# Power.net
KiCad netlist of a schematic drawn in Altium Designer
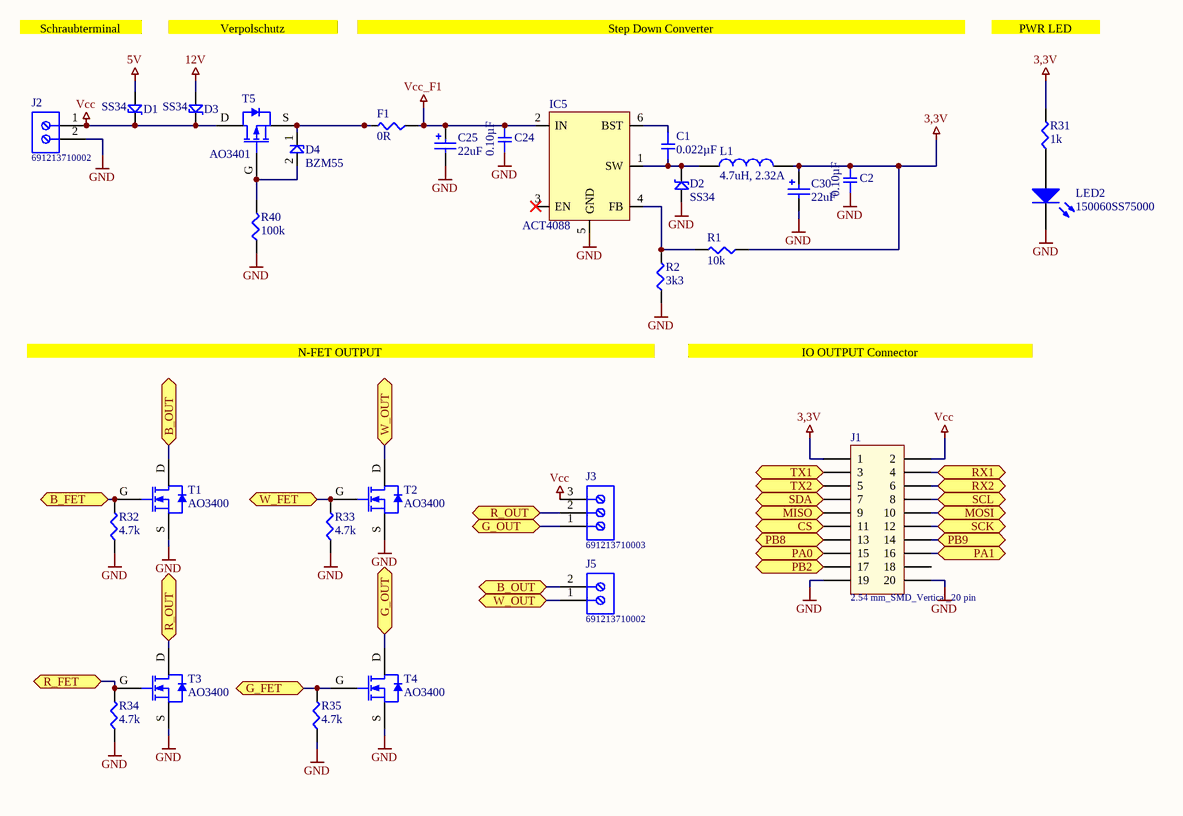
[diagram p0: Power.SchDoc]

(export (version "E")
  (design (tool "Eeschema 10.0.6"))
  (components
    (comp (ref "C1")
      (value "0.022µF")
      (footprint "SMD-0603C")
      (description "CAP CER 0.022UF 50V X7R 0603")
      (fields
        (field (name "DIGI-KEY PART NUMBER") "490-5851-1-ND")
        (field (name "PART NUMBER") "GCJ188R71H223KA01D")
      )
      (libsource (lib "capacitor_murata_0603") (part "GCJ188R71H223KA01D"))
    )
    (comp (ref "C2")
      (value "0.10µF")
      (footprint "SMD-0603C")
      (description "CAP CER 0.1UF 16V X7R 0603")
      (fields
        (field (name "DIGI-KEY PART NUMBER") "490-8015-1-ND")
        (field (name "PART NUMBER") "GCM188R71C104KA37J")
      )
      (libsource (lib "capacitor_murata_0603") (part "GCM188R71C104KA37J"))
    )
    (comp (ref "C24")
      (value "0.10µF")
      (footprint "SMD-0603C")
      (description "CAP CER 0.1UF 16V X7R 0603")
      (fields
        (field (name "DIGI-KEY PART NUMBER") "490-8015-1-ND")
        (field (name "PART NUMBER") "GCM188R71C104KA37J")
      )
      (libsource (lib "capacitor_murata_0603") (part "GCM188R71C104KA37J"))
    )
    (comp (ref "C25")
      (value "22uF")
      (footprint "WCAP-ASLI_4x5.5")
      (description "WCAP-ASLI Aluminum Electrolytic Capacitors, size Ф4x5.5mm, 6.3V DC, 22uF")
      (fields (field (name "PART NUMBER") "865080140001") (field (name "PUBLISHER") "Wurth Elektronik"))
      (libsource (lib "ALTIUM-WCAP-ASLI-rev17a") (part "865080140001"))
    )
    (comp (ref "C30")
      (value "22uF")
      (footprint "WCAP-ASLI_4x5.5")
      (description "WCAP-ASLI Aluminum Electrolytic Capacitors, size Ф4x5.5mm, 6.3V DC, 22uF")
      (fields (field (name "PART NUMBER") "865080140001") (field (name "PUBLISHER") "Wurth Elektronik"))
      (libsource (lib "ALTIUM-WCAP-ASLI-rev17a") (part "865080140001"))
    )
    (comp (ref "D1")
      (value "SS34")
      (footprint "B240A")
      (description "Shottkydiode")
      (libsource (lib "MyLibs") (part "B240A"))
    )
    (comp (ref "D2")
      (value "SS34")
      (footprint "B240A")
      (description "Shottkydiode")
      (libsource (lib "MyLibs") (part "B240A"))
    )
    (comp (ref "D3")
      (value "SS34")
      (footprint "B240A")
      (description "Shottkydiode")
      (libsource (lib "MyLibs") (part "B240A"))
    )
    (comp (ref "D4") (value "BZM55") (footprint "SMD-0603-RES") (libsource (lib "MyLibs") (part "BZM55")))
    (comp (ref "F1")
      (value "0R")
      (footprint "SMD-0603-RES")
      (description "RES SMD 1K OHM 1% 1/10W 0603")
      (fields
        (field (name "PART NUMBER") "ERJ-3EKF1001V")
        (field (name "DIGI-KEY PART NUMBER") "P1.00KHCT-ND")
      )
      (libsource (lib "Panasonic_ERJ_0603") (part "ERJ-3EKF1001V"))
    )
    (comp (ref "IC5") (value "ACT4088") (footprint "SOT23-6") (libsource (lib "MyLibs") (part "ACT4088")))
    (comp (ref "J1")
      (value "2.54 mm_SMD_Vertical_20 pin")
      (footprint "61002021121")
      (description "Pin Header WR-PHD, pitch 2.54 mm, SMD, Vertical, dual row, 20 pin")
      (fields (field (name "PART NUMBER") "61002021121") (field (name "PUBLISHER") "Wurth Elektronik"))
      (libsource (lib "Altium_WR-PHD_PIN_HEADER_2_54 (rev18a)") (part "61002021121"))
    )
    (comp (ref "J2")
      (value "691213710002")
      (footprint "691213710002")
      (description "Serie 213 - 5.00 mm Horizontal Entry Modular with RisingCage Clamp WR-TBL, 2 pin")
      (fields (field (name "PUBLISHER") "Wurth Elektronik"))
      (libsource (lib "Altium_TBL_RISING_CAGE_SYSTEM (rev18b)") (part "691213710002"))
    )
    (comp (ref "J3")
      (value "691213710003")
      (footprint "691213710003")
      (description "Serie 213 - 5.00 mm Horizontal Entry Modular with RisingCage Clamp WR-TBL, 3 pin")
      (fields (field (name "PUBLISHER") "Wurth Elektronik"))
      (libsource (lib "Altium_TBL_RISING_CAGE_SYSTEM (rev18b)") (part "691213710003"))
    )
    (comp (ref "J5")
      (value "691213710002")
      (footprint "691213710002")
      (description "Serie 213 - 5.00 mm Horizontal Entry Modular with RisingCage Clamp WR-TBL, 2 pin")
      (fields (field (name "PUBLISHER") "Wurth Elektronik"))
      (libsource (lib "Altium_TBL_RISING_CAGE_SYSTEM (rev18b)") (part "691213710002"))
    )
    (comp (ref "L1")
      (value "4.7uH, 2.32A")
      (footprint "WE-PD_7332")
      (description "WE-PD SMT Power Inductor, size 7332, 4.7uH, 2.32A")
      (fields (field (name "PART NUMBER") "744778004") (field (name "PUBLISHER") "Wurth Elektronik"))
      (libsource (lib "ALTIUM-WE-PD-rev19b") (part "744778004"))
    )
    (comp (ref "LED2")
      (value "150060SS75000")
      (footprint "0603_A")
      (description "SMD mono-color Chip LED, WL-SMCW, Super Red")
      (libsource (lib "WL-SMCW SMD chip LED top view mono-color waterclear") (part "150060SS75000"))
    )
    (comp (ref "R1")
      (value "10k")
      (footprint "SMD-0603-RES")
      (description "RES SMD 1K OHM 1% 1/10W 0603")
      (fields
        (field (name "PART NUMBER") "ERJ-3EKF1001V")
        (field (name "DIGI-KEY PART NUMBER") "P1.00KHCT-ND")
      )
      (libsource (lib "Panasonic_ERJ_0603") (part "ERJ-3EKF1001V"))
    )
    (comp (ref "R2")
      (value "3k3")
      (footprint "SMD-0603-RES")
      (description "RES SMD 1K OHM 1% 1/10W 0603")
      (fields
        (field (name "PART NUMBER") "ERJ-3EKF1001V")
        (field (name "DIGI-KEY PART NUMBER") "P1.00KHCT-ND")
      )
      (libsource (lib "Panasonic_ERJ_0603") (part "ERJ-3EKF1001V"))
    )
    (comp (ref "R31")
      (value "1k")
      (footprint "SMD-0603-RES")
      (description "RES SMD 1K OHM 1% 1/10W 0603")
      (fields
        (field (name "PART NUMBER") "ERJ-3EKF1001V")
        (field (name "DIGI-KEY PART NUMBER") "P1.00KHCT-ND")
      )
      (libsource (lib "Panasonic_ERJ_0603") (part "ERJ-3EKF1001V"))
    )
    (comp (ref "R32")
      (value "4.7k")
      (footprint "SMD-0603-RES")
      (description "RES SMD 4.7K OHM 1% 1/10W 0603")
      (fields
        (field (name "PART NUMBER") "ERJ-3EKF4701V")
        (field (name "DIGI-KEY PART NUMBER") "P4.70KHCT-ND")
      )
      (libsource (lib "Panasonic_ERJ_0603") (part "ERJ-3EKF4701V"))
    )
    (comp (ref "R33")
      (value "4.7k")
      (footprint "SMD-0603-RES")
      (description "RES SMD 4.7K OHM 1% 1/10W 0603")
      (fields
        (field (name "PART NUMBER") "ERJ-3EKF4701V")
        (field (name "DIGI-KEY PART NUMBER") "P4.70KHCT-ND")
      )
      (libsource (lib "Panasonic_ERJ_0603") (part "ERJ-3EKF4701V"))
    )
    (comp (ref "R34")
      (value "4.7k")
      (footprint "SMD-0603-RES")
      (description "RES SMD 4.7K OHM 1% 1/10W 0603")
      (fields
        (field (name "PART NUMBER") "ERJ-3EKF4701V")
        (field (name "DIGI-KEY PART NUMBER") "P4.70KHCT-ND")
      )
      (libsource (lib "Panasonic_ERJ_0603") (part "ERJ-3EKF4701V"))
    )
    (comp (ref "R35")
      (value "4.7k")
      (footprint "SMD-0603-RES")
      (description "RES SMD 4.7K OHM 1% 1/10W 0603")
      (fields
        (field (name "PART NUMBER") "ERJ-3EKF4701V")
        (field (name "DIGI-KEY PART NUMBER") "P4.70KHCT-ND")
      )
      (libsource (lib "Panasonic_ERJ_0603") (part "ERJ-3EKF4701V"))
    )
    (comp (ref "R40")
      (value "100k")
      (footprint "SMD-0603-RES")
      (description "RES SMD 4.7K OHM 1% 1/10W 0603")
      (fields
        (field (name "PART NUMBER") "ERJ-3EKF4701V")
        (field (name "DIGI-KEY PART NUMBER") "P4.70KHCT-ND")
      )
      (libsource (lib "Panasonic_ERJ_0603") (part "ERJ-3EKF4701V"))
    )
    (comp (ref "T1")
      (value "AO3400")
      (footprint "SOT23")
      (description "AO3400 MOSFET 30V")
      (libsource (lib "MyLibs") (part "AO3400"))
    )
    (comp (ref "T2")
      (value "AO3400")
      (footprint "SOT23")
      (description "AO3400 MOSFET 30V")
      (libsource (lib "MyLibs") (part "AO3400"))
    )
    (comp (ref "T3")
      (value "AO3400")
      (footprint "SOT23")
      (description "AO3400 MOSFET 30V")
      (libsource (lib "MyLibs") (part "AO3400"))
    )
    (comp (ref "T4")
      (value "AO3400")
      (footprint "SOT23")
      (description "AO3400 MOSFET 30V")
      (libsource (lib "MyLibs") (part "AO3400"))
    )
    (comp (ref "T5")
      (value "AO3401")
      (footprint "SOT23")
      (description "AO3401 MOSFET 30V")
      (libsource (lib "MyLibs") (part "AO3401"))
    )
  )
  (nets
    (net (code "1") (name "/B_FET") (class "Default")
      (node (ref "R32") (pin "2") (pinfunction "2_2") (pintype "passive"))
      (node (ref "T1") (pin "G") (pinfunction "G_G") (pintype "passive"))
    )
    (net (code "2") (name "/B_OUT") (class "Default")
      (node (ref "J5") (pin "2") (pinfunction "2_2") (pintype "passive"))
      (node (ref "T1") (pin "D") (pinfunction "D_D") (pintype "passive"))
    )
    (net (code "3") (name "/CS") (class "Default")
      (node (ref "J1") (pin "11") (pinfunction "11_11") (pintype "passive"))
    )
    (net (code "4") (name "/G_FET") (class "Default")
      (node (ref "R35") (pin "2") (pinfunction "2_2") (pintype "passive"))
      (node (ref "T4") (pin "G") (pinfunction "G_G") (pintype "passive"))
    )
    (net (code "5") (name "/G_OUT") (class "Default")
      (node (ref "J3") (pin "1") (pinfunction "1_1") (pintype "passive"))
      (node (ref "T4") (pin "D") (pinfunction "D_D") (pintype "passive"))
    )
    (net (code "6") (name "/MISO") (class "Default")
      (node (ref "J1") (pin "9") (pinfunction "9_9") (pintype "passive"))
    )
    (net (code "7") (name "/MOSI") (class "Default")
      (node (ref "J1") (pin "10") (pinfunction "10_10") (pintype "passive"))
    )
    (net (code "8") (name "/PA0") (class "Default")
      (node (ref "J1") (pin "15") (pinfunction "15_15") (pintype "passive"))
    )
    (net (code "9") (name "/PA1") (class "Default")
      (node (ref "J1") (pin "16") (pinfunction "16_16") (pintype "passive"))
    )
    (net (code "10") (name "/PB2") (class "Default")
      (node (ref "J1") (pin "17") (pinfunction "17_17") (pintype "passive"))
    )
    (net (code "11") (name "/PB8") (class "Default")
      (node (ref "J1") (pin "13") (pinfunction "13_13") (pintype "passive"))
    )
    (net (code "12") (name "/PB9") (class "Default")
      (node (ref "J1") (pin "14") (pinfunction "14_14") (pintype "passive"))
    )
    (net (code "13") (name "/RX1") (class "Default")
      (node (ref "J1") (pin "4") (pinfunction "4_4") (pintype "passive"))
    )
    (net (code "14") (name "/RX2") (class "Default")
      (node (ref "J1") (pin "6") (pinfunction "6_6") (pintype "passive"))
    )
    (net (code "15") (name "/R_FET") (class "Default")
      (node (ref "R34") (pin "2") (pinfunction "2_2") (pintype "passive"))
      (node (ref "T3") (pin "G") (pinfunction "G_G") (pintype "passive"))
    )
    (net (code "16") (name "/R_OUT") (class "Default")
      (node (ref "J3") (pin "2") (pinfunction "2_2") (pintype "passive"))
      (node (ref "T3") (pin "D") (pinfunction "D_D") (pintype "passive"))
    )
    (net (code "17") (name "/SCK") (class "Default")
      (node (ref "J1") (pin "12") (pinfunction "12_12") (pintype "passive"))
    )
    (net (code "18") (name "/SCL") (class "Default")
      (node (ref "J1") (pin "8") (pinfunction "8_8") (pintype "passive"))
    )
    (net (code "19") (name "/SDA") (class "Default")
      (node (ref "J1") (pin "7") (pinfunction "7_7") (pintype "passive"))
    )
    (net (code "20") (name "/TX1") (class "Default")
      (node (ref "J1") (pin "3") (pinfunction "3_3") (pintype "passive"))
    )
    (net (code "21") (name "/TX2") (class "Default")
      (node (ref "J1") (pin "5") (pinfunction "5_5") (pintype "passive"))
    )
    (net (code "22") (name "/W_FET") (class "Default")
      (node (ref "R33") (pin "2") (pinfunction "2_2") (pintype "passive"))
      (node (ref "T2") (pin "G") (pinfunction "G_G") (pintype "passive"))
    )
    (net (code "23") (name "/W_OUT") (class "Default")
      (node (ref "J5") (pin "1") (pinfunction "1_1") (pintype "passive"))
      (node (ref "T2") (pin "D") (pinfunction "D_D") (pintype "passive"))
    )
    (net (code "24") (name "3,3V") (class "Default")
      (node (ref "C2") (pin "1") (pinfunction "1_1") (pintype "passive"))
      (node (ref "C30") (pin "1") (pinfunction "P_1") (pintype "passive"))
      (node (ref "J1") (pin "1") (pinfunction "1_1") (pintype "passive"))
      (node (ref "L1") (pin "2") (pinfunction "2_2") (pintype "passive"))
      (node (ref "R1") (pin "1") (pinfunction "1_1") (pintype "passive"))
      (node (ref "R31") (pin "2") (pinfunction "2_2") (pintype "passive"))
    )
    (net (code "25") (name "5V") (class "Default")
      (node (ref "D1") (pin "A") (pinfunction "A_A") (pintype "passive"))
    )
    (net (code "26") (name "12V") (class "Default")
      (node (ref "D3") (pin "A") (pinfunction "A_A") (pintype "passive"))
    )
    (net (code "27") (name "GND") (class "Default")
      (node (ref "C2") (pin "2") (pinfunction "2_2") (pintype "passive"))
      (node (ref "C24") (pin "2") (pinfunction "2_2") (pintype "passive"))
      (node (ref "C25") (pin "2") (pinfunction "N_2") (pintype "passive"))
      (node (ref "C30") (pin "2") (pinfunction "N_2") (pintype "passive"))
      (node (ref "D2") (pin "A") (pinfunction "A_A") (pintype "passive"))
      (node (ref "IC5") (pin "5") (pinfunction "GND_5") (pintype "passive"))
      (node (ref "J1") (pin "19") (pinfunction "19_19") (pintype "passive"))
      (node (ref "J1") (pin "20") (pinfunction "20_20") (pintype "passive"))
      (node (ref "J2") (pin "2") (pinfunction "2_2") (pintype "passive"))
      (node (ref "LED2") (pin "1") (pinfunction "K_1") (pintype "passive"))
      (node (ref "R2") (pin "1") (pinfunction "1_1") (pintype "passive"))
      (node (ref "R32") (pin "1") (pinfunction "1_1") (pintype "passive"))
      (node (ref "R33") (pin "1") (pinfunction "1_1") (pintype "passive"))
      (node (ref "R34") (pin "1") (pinfunction "1_1") (pintype "passive"))
      (node (ref "R35") (pin "1") (pinfunction "1_1") (pintype "passive"))
      (node (ref "R40") (pin "1") (pinfunction "1_1") (pintype "passive"))
      (node (ref "T1") (pin "S") (pinfunction "S_S") (pintype "passive"))
      (node (ref "T2") (pin "S") (pinfunction "S_S") (pintype "passive"))
      (node (ref "T3") (pin "S") (pinfunction "S_S") (pintype "passive"))
      (node (ref "T4") (pin "S") (pinfunction "S_S") (pintype "passive"))
    )
    (net (code "28") (name "Net-(D4-1-Pad2)") (class "Default")
      (node (ref "D4") (pin "2") (pinfunction "1_2") (pintype "passive"))
      (node (ref "R40") (pin "2") (pinfunction "2_2") (pintype "passive"))
      (node (ref "T5") (pin "G") (pinfunction "G_G") (pintype "passive"))
    )
    (net (code "29") (name "Net-(D4-Pad1)") (class "Default")
      (node (ref "D4") (pin "1") (pinfunction "1_1") (pintype "passive"))
      (node (ref "F1") (pin "2") (pinfunction "2_2") (pintype "passive"))
      (node (ref "T5") (pin "S") (pinfunction "S_S") (pintype "passive"))
    )
    (net (code "30") (name "Net-(IC5-BST)") (class "Default")
      (node (ref "C1") (pin "1") (pinfunction "1_1") (pintype "passive"))
      (node (ref "IC5") (pin "6") (pinfunction "BST_6") (pintype "passive"))
    )
    (net (code "31") (name "Net-(IC5-FB)") (class "Default")
      (node (ref "IC5") (pin "4") (pinfunction "FB_4") (pintype "passive"))
      (node (ref "R1") (pin "2") (pinfunction "2_2") (pintype "passive"))
      (node (ref "R2") (pin "2") (pinfunction "2_2") (pintype "passive"))
    )
    (net (code "32") (name "Net-(IC5-SW)") (class "Default")
      (node (ref "C1") (pin "2") (pinfunction "2_2") (pintype "passive"))
      (node (ref "D2") (pin "K") (pinfunction "K_K") (pintype "passive"))
      (node (ref "IC5") (pin "1") (pinfunction "SW_1") (pintype "passive"))
      (node (ref "L1") (pin "1") (pinfunction "1_1") (pintype "passive"))
    )
    (net (code "33") (name "Net-(LED2-A)") (class "Default")
      (node (ref "LED2") (pin "2") (pinfunction "A_2") (pintype "passive"))
      (node (ref "R31") (pin "1") (pinfunction "1_1") (pintype "passive"))
    )
    (net (code "34") (name "Vcc") (class "Default")
      (node (ref "D1") (pin "K") (pinfunction "K_K") (pintype "passive"))
      (node (ref "D3") (pin "K") (pinfunction "K_K") (pintype "passive"))
      (node (ref "J1") (pin "2") (pinfunction "2_2") (pintype "passive"))
      (node (ref "J2") (pin "1") (pinfunction "1_1") (pintype "passive"))
      (node (ref "J3") (pin "3") (pinfunction "3_3") (pintype "passive"))
      (node (ref "T5") (pin "D") (pinfunction "D_D") (pintype "passive"))
    )
    (net (code "35") (name "Vcc_F1") (class "Default")
      (node (ref "C24") (pin "1") (pinfunction "1_1") (pintype "passive"))
      (node (ref "C25") (pin "1") (pinfunction "P_1") (pintype "passive"))
      (node (ref "F1") (pin "1") (pinfunction "1_1") (pintype "passive"))
      (node (ref "IC5") (pin "2") (pinfunction "IN_2") (pintype "passive"))
    )
    (net (code "36") (name "unconnected-(IC5-EN-Pad3)") (class "Default")
      (node (ref "IC5") (pin "3") (pinfunction "EN_3") (pintype "passive+no_connect"))
    )
    (net (code "37") (name "unconnected-(J1-Pad18)") (class "Default")
      (node (ref "J1") (pin "18") (pinfunction "18_18") (pintype "passive"))
    )
  )
)
